# E17-PDU-4-REGULATORS.net
KiCad netlist of a schematic drawn in Altium Designer
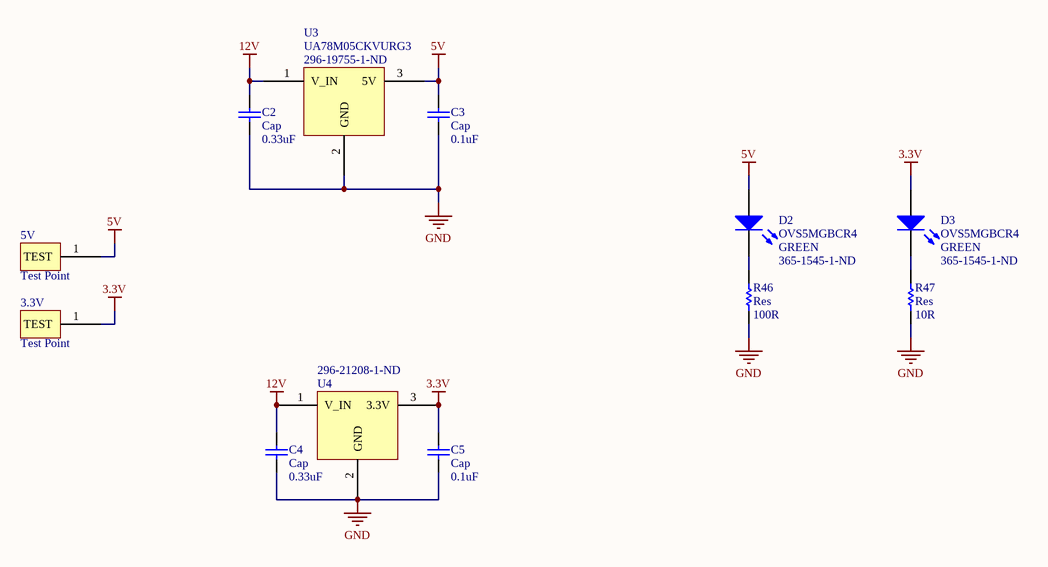
[diagram p0: E17-PDU-4-REGULATORS.SchDoc]

(export (version "E")
  (design (tool "Eeschema 10.0.6"))
  (components
    (comp (ref "3.3V")
      (value "Test Point")
      (footprint "TEST POINT 5000K")
      (description "5000-5004, 5015-5019 Keystone Electronics")
      (libsource (lib "Mechanical_Devices") (part "Test Point"))
    )
    (comp (ref "5V")
      (value "Test Point")
      (footprint "TEST POINT 5000K")
      (description "5000-5004, 5015-5019 Keystone Electronics")
      (libsource (lib "Mechanical_Devices") (part "Test Point"))
    )
    (comp (ref "C2")
      (value "Cap")
      (footprint "C0805")
      (description "Capacitor")
      (fields (field (name "ALTIUM_VALUE") "0.33uF") (field (name "PUBLISHER") "Altium Limited"))
      (libsource (lib "Capacitors") (part "Cap"))
    )
    (comp (ref "C3")
      (value "Cap")
      (footprint "C0805")
      (description "Capacitor")
      (fields (field (name "ALTIUM_VALUE") "0.1uF") (field (name "PUBLISHER") "Altium Limited"))
      (libsource (lib "Capacitors") (part "Cap"))
    )
    (comp (ref "C4")
      (value "Cap")
      (footprint "C0805")
      (description "Capacitor")
      (fields (field (name "ALTIUM_VALUE") "0.33uF") (field (name "PUBLISHER") "Altium Limited"))
      (libsource (lib "Capacitors") (part "Cap"))
    )
    (comp (ref "C5")
      (value "Cap")
      (footprint "C0805")
      (description "Capacitor")
      (fields (field (name "ALTIUM_VALUE") "0.1uF") (field (name "PUBLISHER") "Altium Limited"))
      (libsource (lib "Capacitors") (part "Cap"))
    )
    (comp (ref "D2")
      (value "OVS5MGBCR4")
      (footprint "OVS5MGBCR4")
      (description "Typical GREEN LED")
      (fields
        (field (name "COLOUR") "GREEN")
        (field (name "SUPPLIER PART NUMBER 1") "365-1545-1-ND")
        (field (name "PUBLISHER") "Altium Limited")
      )
      (libsource (lib "LEDs") (part "OVS5MGBCR4"))
    )
    (comp (ref "D3")
      (value "OVS5MGBCR4")
      (footprint "OVS5MGBCR4")
      (description "Typical GREEN LED")
      (fields
        (field (name "COLOUR") "GREEN")
        (field (name "SUPPLIER PART NUMBER 1") "365-1545-1-ND")
        (field (name "PUBLISHER") "Altium Limited")
      )
      (libsource (lib "LEDs") (part "OVS5MGBCR4"))
    )
    (comp (ref "R46")
      (value "Res")
      (footprint "2012[0805]")
      (description "Surface Mount Resistor")
      (fields (field (name "ALTIUM_VALUE") "100R") (field (name "PUBLISHER") "Altium Limited"))
      (libsource (lib "Resistors") (part "Res"))
    )
    (comp (ref "R47")
      (value "Res")
      (footprint "2012[0805]")
      (description "Surface Mount Resistor")
      (fields (field (name "ALTIUM_VALUE") "10R") (field (name "PUBLISHER") "Altium Limited"))
      (libsource (lib "Resistors") (part "Res"))
    )
    (comp (ref "U3")
      (value "UA78M05CKVURG3")
      (footprint "TO-252-3")
      (description "5.0V Regulator")
      (fields (field (name "SUPPLIER PART NUMBER 1") "296-19755-1-ND"))
      (libsource (lib "Voltage Regulation") (part "UA78M05CKVURG3"))
    )
    (comp (ref "U4")
      (value "UA78M33CKVURG3")
      (footprint "TO-252-3")
      (description "3.3V Regulator")
      (fields (field (name "SUPPLIER PART NUMBER 1") "296-21208-1-ND"))
      (libsource (lib "Voltage Regulation") (part "UA78M33CKVURG3"))
    )
  )
  (nets
    (net (code "1") (name "3.3V") (class "Default")
      (node (ref "3.3V") (pin "1") (pinfunction "TEST_1") (pintype "passive"))
      (node (ref "C5") (pin "2") (pinfunction "2_2") (pintype "passive"))
      (node (ref "D3") (pin "1") (pinfunction "A_1") (pintype "passive"))
      (node (ref "U4") (pin "3") (pinfunction "3.3V_3") (pintype "passive"))
    )
    (net (code "2") (name "5V") (class "Default")
      (node (ref "5V") (pin "1") (pinfunction "TEST_1") (pintype "passive"))
      (node (ref "C3") (pin "2") (pinfunction "2_2") (pintype "passive"))
      (node (ref "D2") (pin "1") (pinfunction "A_1") (pintype "passive"))
      (node (ref "U3") (pin "3") (pinfunction "5V_3") (pintype "passive"))
    )
    (net (code "3") (name "12V") (class "Default")
      (node (ref "C2") (pin "2") (pinfunction "2_2") (pintype "passive"))
      (node (ref "C4") (pin "2") (pinfunction "2_2") (pintype "passive"))
      (node (ref "U3") (pin "1") (pinfunction "V_IN_1") (pintype "passive"))
      (node (ref "U4") (pin "1") (pinfunction "V_IN_1") (pintype "passive"))
    )
    (net (code "4") (name "GND") (class "Default")
      (node (ref "C2") (pin "1") (pinfunction "1_1") (pintype "passive"))
      (node (ref "C3") (pin "1") (pinfunction "1_1") (pintype "passive"))
      (node (ref "C4") (pin "1") (pinfunction "1_1") (pintype "passive"))
      (node (ref "C5") (pin "1") (pinfunction "1_1") (pintype "passive"))
      (node (ref "R46") (pin "2") (pinfunction "2_2") (pintype "passive"))
      (node (ref "R47") (pin "2") (pinfunction "2_2") (pintype "passive"))
      (node (ref "U3") (pin "2") (pinfunction "GND_2") (pintype "passive"))
      (node (ref "U4") (pin "2") (pinfunction "GND_2") (pintype "passive"))
    )
    (net (code "5") (name "Net-(D2-K)") (class "Default")
      (node (ref "D2") (pin "2") (pinfunction "K_2") (pintype "passive"))
      (node (ref "R46") (pin "1") (pinfunction "1_1") (pintype "passive"))
    )
    (net (code "6") (name "Net-(D3-K)") (class "Default")
      (node (ref "D3") (pin "2") (pinfunction "K_2") (pintype "passive"))
      (node (ref "R47") (pin "1") (pinfunction "1_1") (pintype "passive"))
    )
  )
)
